# robot_large.net
KiCad netlist of a schematic drawn in EAGLE
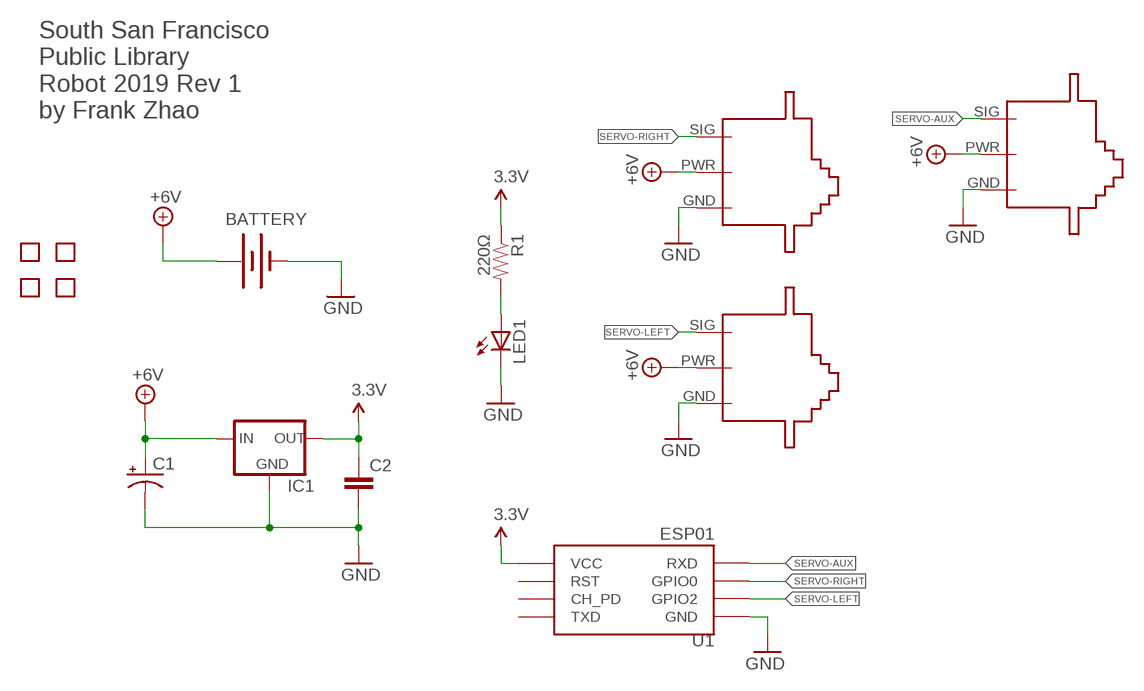
[diagram p0: schematic, sheet 1]

(export (version "E")
  (design (tool "Eeschema 10.0.6"))
  (components
    (comp (ref "BATTERY")
      (value "BATTERY-WIRE-CONN")
      (footprint "eagle-import:BATT-WIRE-CONN")
      (libsource (lib "eagle-import") (part "BATTERY-WIRE-CONN"))
    )
    (comp (ref "C1")
      (value "CAP_POLPTH1")
      (footprint "eagle-import:CPOL-RADIAL-100UF-25V")
      (libsource (lib "eagle-import") (part "CAP_POLPTH1"))
    )
    (comp (ref "C2")
      (value "CAPPTH")
      (footprint "eagle-import:CAP-PTH-SMALL")
      (libsource (lib "eagle-import") (part "CAPPTH"))
    )
    (comp (ref "IC1")
      (value "V_REG_78XXTO-92")
      (footprint "eagle-import:TO-92")
      (libsource (lib "eagle-import") (part "V_REG_78XXTO-92"))
    )
    (comp (ref "LED1")
      (value "LED5MM")
      (footprint "eagle-import:LED5MM")
      (libsource (lib "eagle-import") (part "LED5MM"))
    )
    (comp (ref "M1")
      (value "SERVO-FLIPPED")
      (footprint "eagle-import:SERVO-FLIPPED")
      (libsource (lib "eagle-import") (part "SERVO-FLIPPED"))
    )
    (comp (ref "M2")
      (value "SERVO-1")
      (footprint "eagle-import:SERVO")
      (libsource (lib "eagle-import") (part "SERVO-1"))
    )
    (comp (ref "M3")
      (value "SERVO-1")
      (footprint "eagle-import:SERVO")
      (libsource (lib "eagle-import") (part "SERVO-1"))
    )
    (comp (ref "R1")
      (value "220Ω")
      (footprint "eagle-import:AXIAL-0.3-NOVAL")
      (libsource (lib "eagle-import") (part "RESISTORAXIAL-0.3-NOVAL"))
    )
    (comp (ref "U$9")
      (value "TEXT-INFO")
      (footprint "eagle-import:TEXT-INFO")
      (libsource (lib "eagle-import") (part "TEXT-INFO"))
    )
    (comp (ref "U$10")
      (value "HOLE")
      (footprint "eagle-import:HOLE-2MM")
      (libsource (lib "eagle-import") (part "HOLE"))
    )
    (comp (ref "U$11")
      (value "HOLE")
      (footprint "eagle-import:HOLE-2MM")
      (libsource (lib "eagle-import") (part "HOLE"))
    )
    (comp (ref "U$12")
      (value "HOLE")
      (footprint "eagle-import:HOLE-2MM")
      (libsource (lib "eagle-import") (part "HOLE"))
    )
    (comp (ref "U$13")
      (value "HOLE")
      (footprint "eagle-import:HOLE-2MM")
      (libsource (lib "eagle-import") (part "HOLE"))
    )
    (comp (ref "U1")
      (value "ESP01")
      (footprint "eagle-import:ESP01")
      (libsource (lib "eagle-import") (part "ESP01"))
    )
  )
  (nets
    (net (code "1") (name "+6V") (class "Default")
      (node (ref "BATTERY") (pin "POS") (pinfunction "+_POS") (pintype "power_in"))
      (node (ref "C1") (pin "1") (pinfunction "+_1") (pintype "passive"))
      (node (ref "IC1") (pin "2") (pinfunction "IN_2") (pintype "input"))
      (node (ref "M1") (pin "PWR") (pinfunction "PWR_PWR") (pintype "bidirectional"))
      (node (ref "M2") (pin "PWR") (pinfunction "PWR_PWR") (pintype "bidirectional"))
      (node (ref "M3") (pin "PWR") (pinfunction "PWR_PWR") (pintype "bidirectional"))
    )
    (net (code "2") (name "3.3V") (class "Default")
      (node (ref "C2") (pin "1") (pinfunction "1_1") (pintype "passive"))
      (node (ref "IC1") (pin "3") (pinfunction "OUT_3") (pintype "output"))
      (node (ref "R1") (pin "P$1") (pinfunction "1_P$1") (pintype "passive"))
      (node (ref "U1") (pin "VCC") (pinfunction "VCC_VCC") (pintype "bidirectional"))
    )
    (net (code "3") (name "GND") (class "Default")
      (node (ref "BATTERY") (pin "NEG") (pinfunction "-_NEG") (pintype "power_in"))
      (node (ref "C1") (pin "2") (pinfunction "-_2") (pintype "passive"))
      (node (ref "C2") (pin "2") (pinfunction "2_2") (pintype "passive"))
      (node (ref "IC1") (pin "1") (pinfunction "GND_1") (pintype "input"))
      (node (ref "LED1") (pin "K") (pinfunction "C_K") (pintype "passive"))
      (node (ref "M1") (pin "GND") (pinfunction "GND_GND") (pintype "bidirectional"))
      (node (ref "M2") (pin "GND") (pinfunction "GND_GND") (pintype "bidirectional"))
      (node (ref "M3") (pin "GND") (pinfunction "GND_GND") (pintype "bidirectional"))
      (node (ref "U1") (pin "GND") (pinfunction "GND_GND") (pintype "bidirectional"))
    )
    (net (code "4") (name "Net-(R1-2)") (class "Default")
      (node (ref "LED1") (pin "A") (pinfunction "A_A") (pintype "passive"))
      (node (ref "R1") (pin "P$2") (pinfunction "2_P$2") (pintype "passive"))
    )
    (net (code "5") (name "SERVO-AUX") (class "Default")
      (node (ref "M3") (pin "SIG") (pinfunction "SIG_SIG") (pintype "bidirectional"))
      (node (ref "U1") (pin "RX") (pinfunction "RXD_RX") (pintype "bidirectional"))
    )
    (net (code "6") (name "SERVO-LEFT") (class "Default")
      (node (ref "M1") (pin "SIG") (pinfunction "SIG_SIG") (pintype "bidirectional"))
      (node (ref "U1") (pin "GPIO2") (pinfunction "GPIO2_GPIO2") (pintype "bidirectional"))
    )
    (net (code "7") (name "SERVO-RIGHT") (class "Default")
      (node (ref "M2") (pin "SIG") (pinfunction "SIG_SIG") (pintype "bidirectional"))
      (node (ref "U1") (pin "GPIO0") (pinfunction "GPIO0_GPIO0") (pintype "bidirectional"))
    )
    (net (code "8") (name "unconnected-(U1-PadCH_PD)") (class "Default")
      (node (ref "U1") (pin "CH_PD") (pinfunction "CH_PD_CH_PD") (pintype "bidirectional"))
    )
    (net (code "9") (name "unconnected-(U1-PadRST)") (class "Default")
      (node (ref "U1") (pin "RST") (pinfunction "RST_RST") (pintype "bidirectional"))
    )
    (net (code "10") (name "unconnected-(U1-TXD-PadTX)") (class "Default")
      (node (ref "U1") (pin "TX") (pinfunction "TXD_TX") (pintype "bidirectional"))
    )
  )
)
